# LCD44.net
KiCad netlist of a schematic drawn in EAGLE
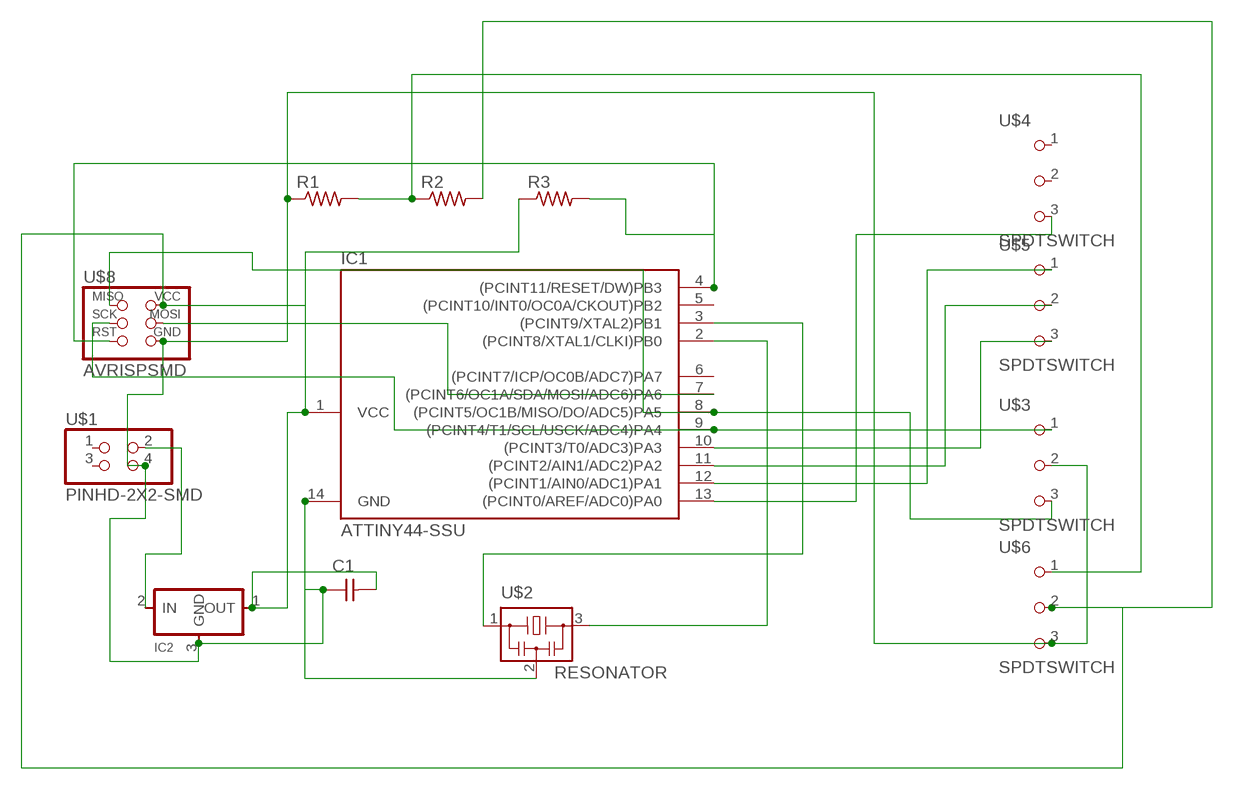
[diagram p0: schematic, sheet 1]

(export (version "E")
  (design (tool "Eeschema 10.0.6"))
  (components
    (comp (ref "C1")
      (value "CAP-UNPOLARIZEDFAB")
      (footprint "eagle-import:C1206FAB")
      (libsource (lib "eagle-import") (part "CAP-UNPOLARIZEDFAB"))
    )
    (comp (ref "IC1")
      (value "ATTINY44-SSU")
      (footprint "eagle-import:SOIC14")
      (libsource (lib "eagle-import") (part "ATTINY44-SSU"))
    )
    (comp (ref "IC2")
      (value "REGULATORSOT23")
      (footprint "eagle-import:SOT23")
      (libsource (lib "eagle-import") (part "REGULATORSOT23"))
    )
    (comp (ref "R1")
      (value "RES-US1206FAB")
      (footprint "eagle-import:R1206FAB")
      (libsource (lib "eagle-import") (part "RES-US1206FAB"))
    )
    (comp (ref "R2")
      (value "RES-US1206FAB")
      (footprint "eagle-import:R1206FAB")
      (libsource (lib "eagle-import") (part "RES-US1206FAB"))
    )
    (comp (ref "R3")
      (value "RES-US1206FAB")
      (footprint "eagle-import:R1206FAB")
      (libsource (lib "eagle-import") (part "RES-US1206FAB"))
    )
    (comp (ref "U$1")
      (value "PINHD-2X2-SMD")
      (footprint "eagle-import:2X02SMD")
      (libsource (lib "eagle-import") (part "PINHD-2X2-SMD"))
    )
    (comp (ref "U$2")
      (value "RESONATOR")
      (footprint "eagle-import:EFOBM")
      (libsource (lib "eagle-import") (part "RESONATOR"))
    )
    (comp (ref "U$3")
      (value "SPDTSWITCH")
      (footprint "eagle-import:SPDTSWITCH")
      (libsource (lib "eagle-import") (part "SPDTSWITCH"))
    )
    (comp (ref "U$4")
      (value "SPDTSWITCH")
      (footprint "eagle-import:SPDTSWITCH")
      (libsource (lib "eagle-import") (part "SPDTSWITCH"))
    )
    (comp (ref "U$5")
      (value "SPDTSWITCH")
      (footprint "eagle-import:SPDTSWITCH")
      (libsource (lib "eagle-import") (part "SPDTSWITCH"))
    )
    (comp (ref "U$6")
      (value "SPDTSWITCH")
      (footprint "eagle-import:SPDTSWITCH")
      (libsource (lib "eagle-import") (part "SPDTSWITCH"))
    )
    (comp (ref "U$8")
      (value "AVRISPSMD")
      (footprint "eagle-import:2X03SMD")
      (libsource (lib "eagle-import") (part "AVRISPSMD"))
    )
  )
  (nets
    (net (code "1") (name "Net-(IC1-(PCINT0{slash}AREF{slash}ADC0)PA0)") (class "Default")
      (node (ref "IC1") (pin "13") (pinfunction "(PCINT0/AREF/ADC0)PA0_13") (pintype "bidirectional"))
      (node (ref "U$4") (pin "3") (pinfunction "3_3") (pintype "passive"))
    )
    (net (code "2") (name "Net-(IC1-(PCINT1{slash}AIN0{slash}ADC1)PA1)") (class "Default")
      (node (ref "IC1") (pin "12") (pinfunction "(PCINT1/AIN0/ADC1)PA1_12") (pintype "bidirectional"))
      (node (ref "U$5") (pin "1") (pinfunction "1_1") (pintype "passive"))
    )
    (net (code "3") (name "Net-(IC1-(PCINT2{slash}AIN1{slash}ADC2)PA2)") (class "Default")
      (node (ref "IC1") (pin "11") (pinfunction "(PCINT2/AIN1/ADC2)PA2_11") (pintype "bidirectional"))
      (node (ref "U$5") (pin "2") (pinfunction "2_2") (pintype "passive"))
    )
    (net (code "4") (name "Net-(IC1-(PCINT3{slash}T0{slash}ADC3)PA3)") (class "Default")
      (node (ref "IC1") (pin "10") (pinfunction "(PCINT3/T0/ADC3)PA3_10") (pintype "bidirectional"))
      (node (ref "U$5") (pin "3") (pinfunction "3_3") (pintype "passive"))
    )
    (net (code "5") (name "Net-(IC1-(PCINT4{slash}T1{slash}SCL{slash}USCK{slash}ADC4)PA4)") (class "Default")
      (node (ref "IC1") (pin "9") (pinfunction "(PCINT4/T1/SCL/USCK/ADC4)PA4_9") (pintype "bidirectional"))
      (node (ref "U$3") (pin "1") (pinfunction "1_1") (pintype "passive"))
      (node (ref "U$8") (pin "3") (pinfunction "SCK_3") (pintype "passive"))
    )
    (net (code "6") (name "Net-(IC1-(PCINT5{slash}OC1B{slash}MISO{slash}DO{slash}ADC5)PA5)") (class "Default")
      (node (ref "IC1") (pin "8") (pinfunction "(PCINT5/OC1B/MISO/DO/ADC5)PA5_8") (pintype "bidirectional"))
      (node (ref "U$3") (pin "3") (pinfunction "3_3") (pintype "passive"))
      (node (ref "U$8") (pin "1") (pinfunction "MISO_1") (pintype "passive"))
    )
    (net (code "7") (name "Net-(IC1-(PCINT6{slash}OC1A{slash}SDA{slash}MOSI{slash}ADC6)PA6)") (class "Default")
      (node (ref "IC1") (pin "7") (pinfunction "(PCINT6/OC1A/SDA/MOSI/ADC6)PA6_7") (pintype "bidirectional"))
      (node (ref "U$8") (pin "4") (pinfunction "MOSI_4") (pintype "passive"))
    )
    (net (code "8") (name "Net-(IC1-(PCINT8{slash}XTAL1{slash}CLKI)PB0)") (class "Default")
      (node (ref "IC1") (pin "2") (pinfunction "(PCINT8/XTAL1/CLKI)PB0_2") (pintype "bidirectional"))
      (node (ref "U$2") (pin "3") (pinfunction "3_3") (pintype "passive"))
    )
    (net (code "9") (name "Net-(IC1-(PCINT9{slash}XTAL2)PB1)") (class "Default")
      (node (ref "IC1") (pin "3") (pinfunction "(PCINT9/XTAL2)PB1_3") (pintype "bidirectional"))
      (node (ref "U$2") (pin "1") (pinfunction "1_1") (pintype "passive"))
    )
    (net (code "10") (name "Net-(IC1-(PCINT11{slash}RESET{slash}DW)PB3)") (class "Default")
      (node (ref "IC1") (pin "4") (pinfunction "(PCINT11/RESET/DW)PB3_4") (pintype "bidirectional"))
      (node (ref "R3") (pin "2") (pinfunction "2_2") (pintype "passive"))
      (node (ref "U$8") (pin "5") (pinfunction "RST_5") (pintype "passive"))
    )
    (net (code "11") (name "Net-(IC1-GND)") (class "Default")
      (node (ref "C1") (pin "1") (pinfunction "1_1") (pintype "passive"))
      (node (ref "IC1") (pin "14") (pinfunction "GND_14") (pintype "power_in"))
      (node (ref "IC2") (pin "3") (pinfunction "GND_3") (pintype "bidirectional"))
      (node (ref "R1") (pin "1") (pinfunction "1_1") (pintype "passive"))
      (node (ref "U$1") (pin "4") (pinfunction "4_4") (pintype "passive"))
      (node (ref "U$2") (pin "2") (pinfunction "2_2") (pintype "passive"))
      (node (ref "U$3") (pin "2") (pinfunction "2_2") (pintype "passive"))
      (node (ref "U$6") (pin "3") (pinfunction "3_3") (pintype "passive"))
      (node (ref "U$8") (pin "6") (pinfunction "GND_6") (pintype "passive"))
    )
    (net (code "12") (name "Net-(IC1-VCC)") (class "Default")
      (node (ref "C1") (pin "2") (pinfunction "2_2") (pintype "passive"))
      (node (ref "IC1") (pin "1") (pinfunction "VCC_1") (pintype "power_in"))
      (node (ref "IC2") (pin "1") (pinfunction "OUT_1") (pintype "bidirectional"))
      (node (ref "R2") (pin "2") (pinfunction "2_2") (pintype "passive"))
      (node (ref "R3") (pin "1") (pinfunction "1_1") (pintype "passive"))
      (node (ref "U$6") (pin "2") (pinfunction "2_2") (pintype "passive"))
      (node (ref "U$8") (pin "2") (pinfunction "VCC_2") (pintype "passive"))
    )
    (net (code "13") (name "Net-(IC2-IN)") (class "Default")
      (node (ref "IC2") (pin "2") (pinfunction "IN_2") (pintype "bidirectional"))
      (node (ref "U$1") (pin "2") (pinfunction "2_2") (pintype "passive"))
    )
    (net (code "14") (name "Net-(R1-Pad2)") (class "Default")
      (node (ref "R1") (pin "2") (pinfunction "2_2") (pintype "passive"))
      (node (ref "R2") (pin "1") (pinfunction "1_1") (pintype "passive"))
      (node (ref "U$6") (pin "1") (pinfunction "1_1") (pintype "passive"))
    )
    (net (code "15") (name "unconnected-(IC1-(PCINT7{slash}ICP{slash}OC0B{slash}ADC7)PA7-Pad6)") (class "Default")
      (node (ref "IC1") (pin "6") (pinfunction "(PCINT7/ICP/OC0B/ADC7)PA7_6") (pintype "bidirectional"))
    )
    (net (code "16") (name "unconnected-(IC1-(PCINT10{slash}INT0{slash}OC0A{slash}CKOUT)PB2-Pad5)") (class "Default")
      (node (ref "IC1") (pin "5") (pinfunction "(PCINT10/INT0/OC0A/CKOUT)PB2_5") (pintype "bidirectional"))
    )
    (net (code "17") (name "unconnected-(U$1-Pad1)") (class "Default")
      (node (ref "U$1") (pin "1") (pinfunction "1_1") (pintype "passive"))
    )
    (net (code "18") (name "unconnected-(U$1-Pad3)") (class "Default")
      (node (ref "U$1") (pin "3") (pinfunction "3_3") (pintype "passive"))
    )
    (net (code "19") (name "unconnected-(U$4-Pad1)") (class "Default")
      (node (ref "U$4") (pin "1") (pinfunction "1_1") (pintype "passive"))
    )
    (net (code "20") (name "unconnected-(U$4-Pad2)") (class "Default")
      (node (ref "U$4") (pin "2") (pinfunction "2_2") (pintype "passive"))
    )
  )
)
